# bristol_longshot_development.net
KiCad netlist of a schematic drawn in EAGLE
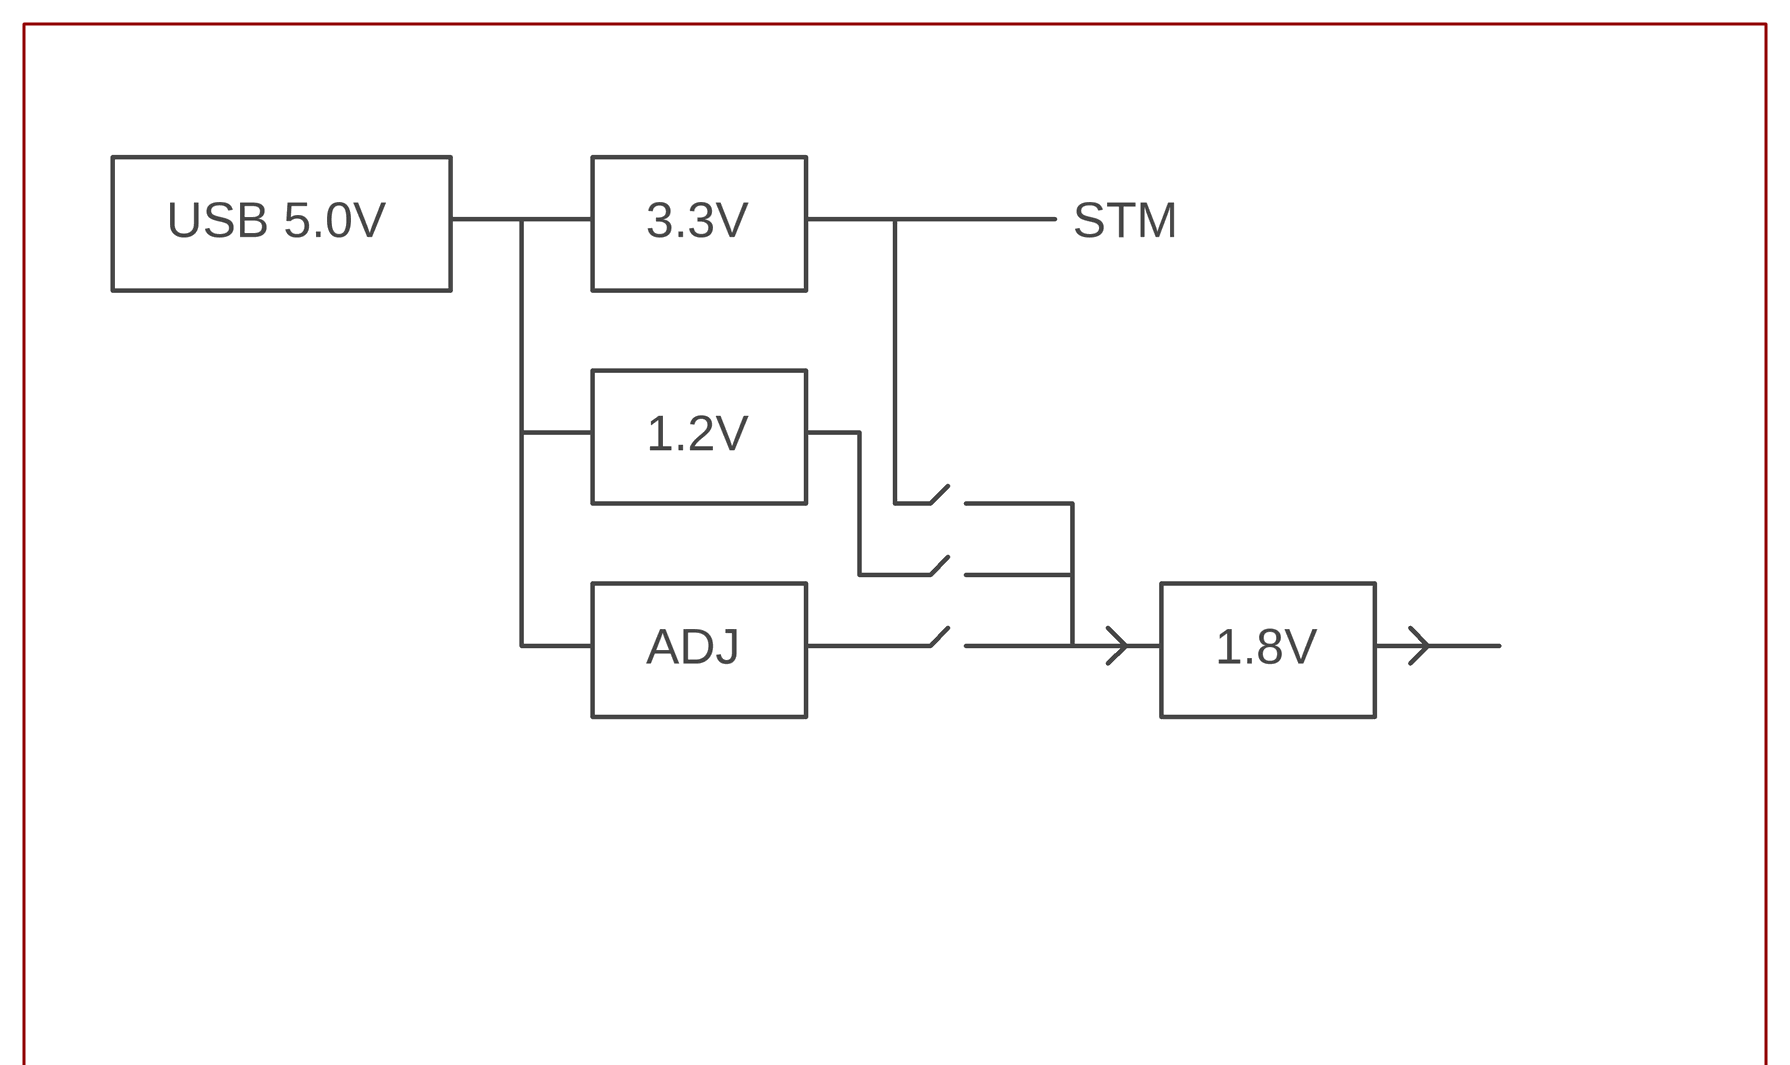
[diagram p0: schematic, sheet 1, part 1 of 3]
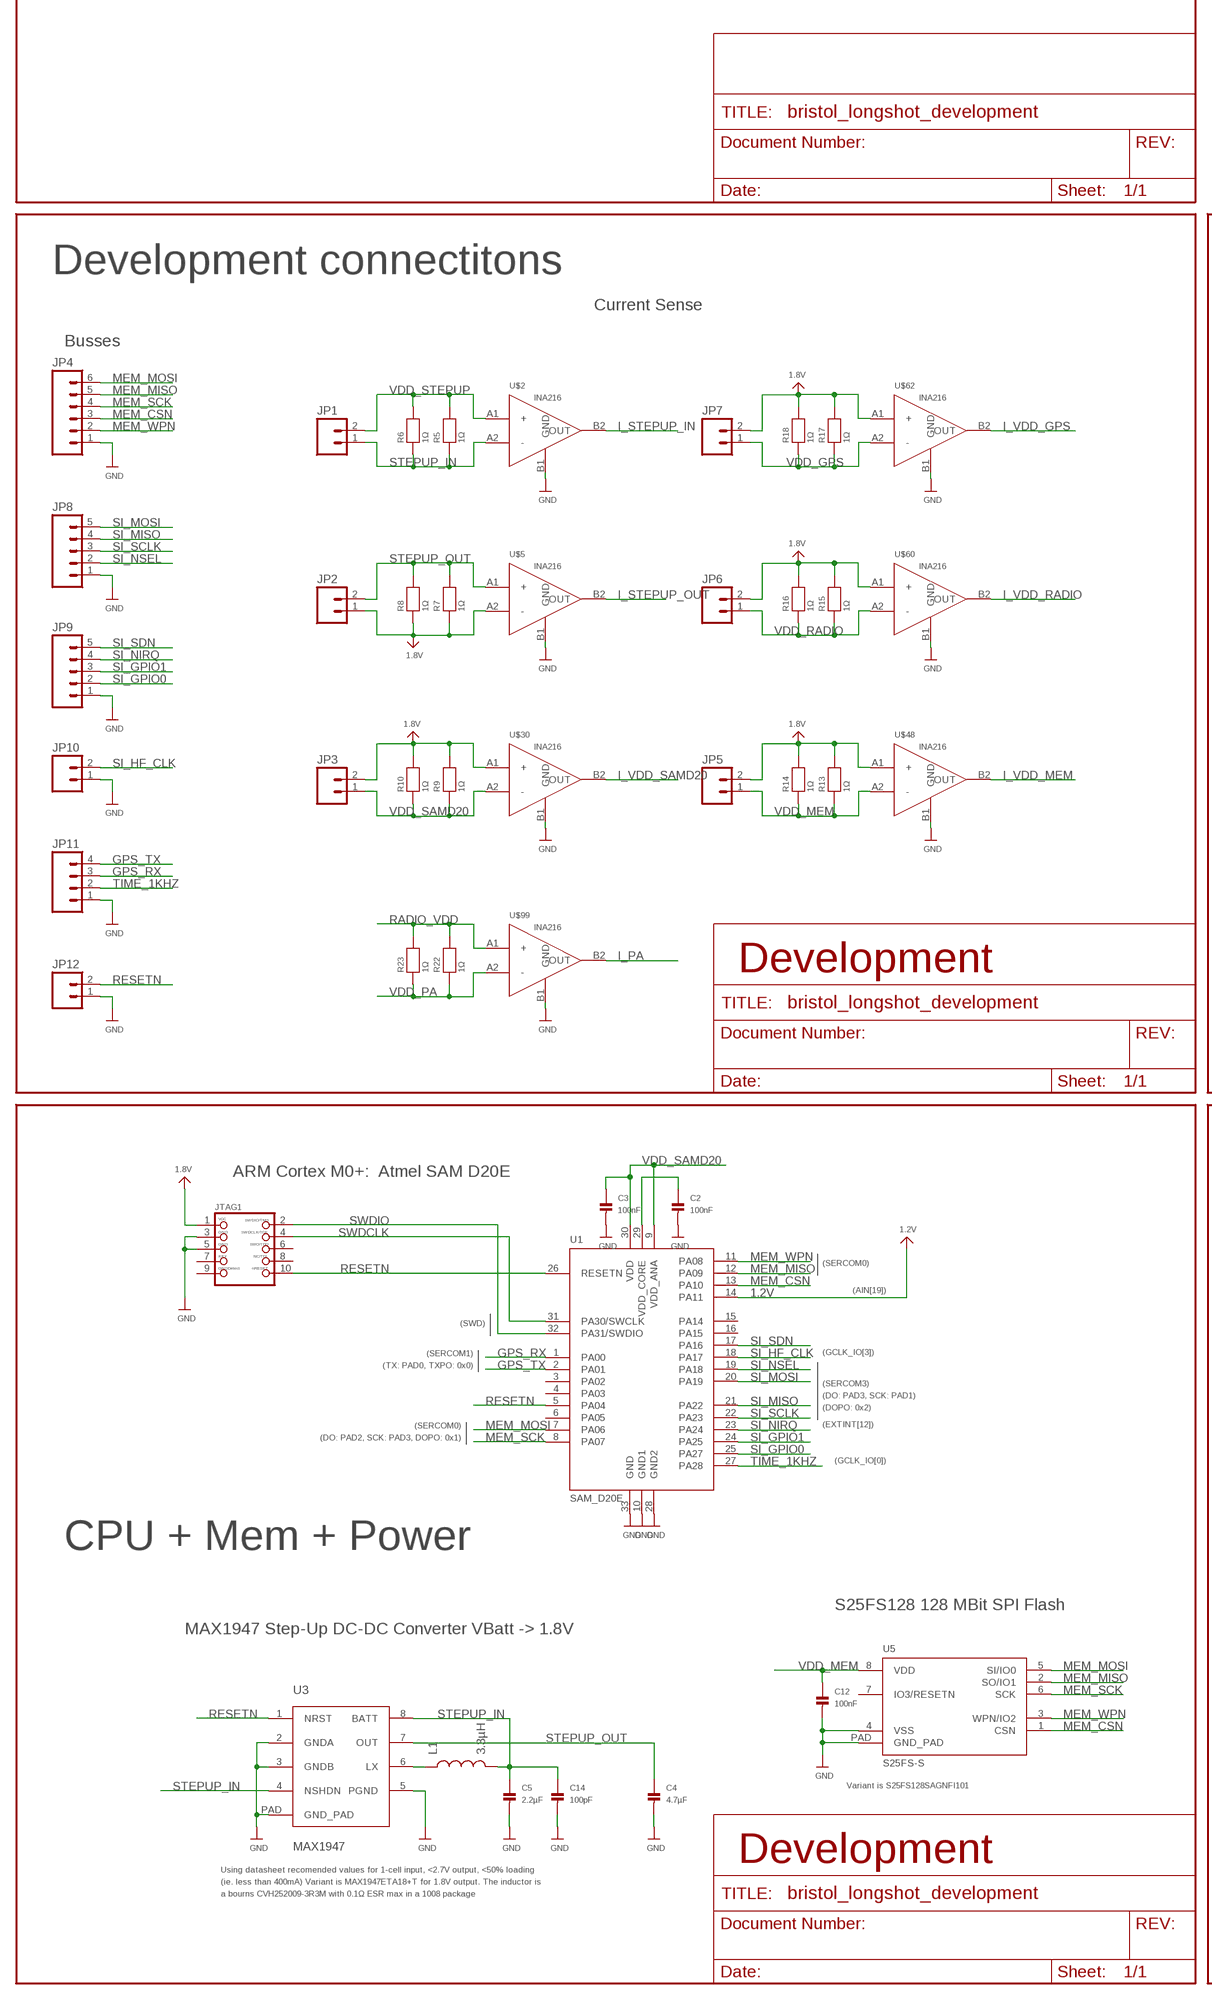
[diagram p1: schematic, sheet 1, part 2 of 3]
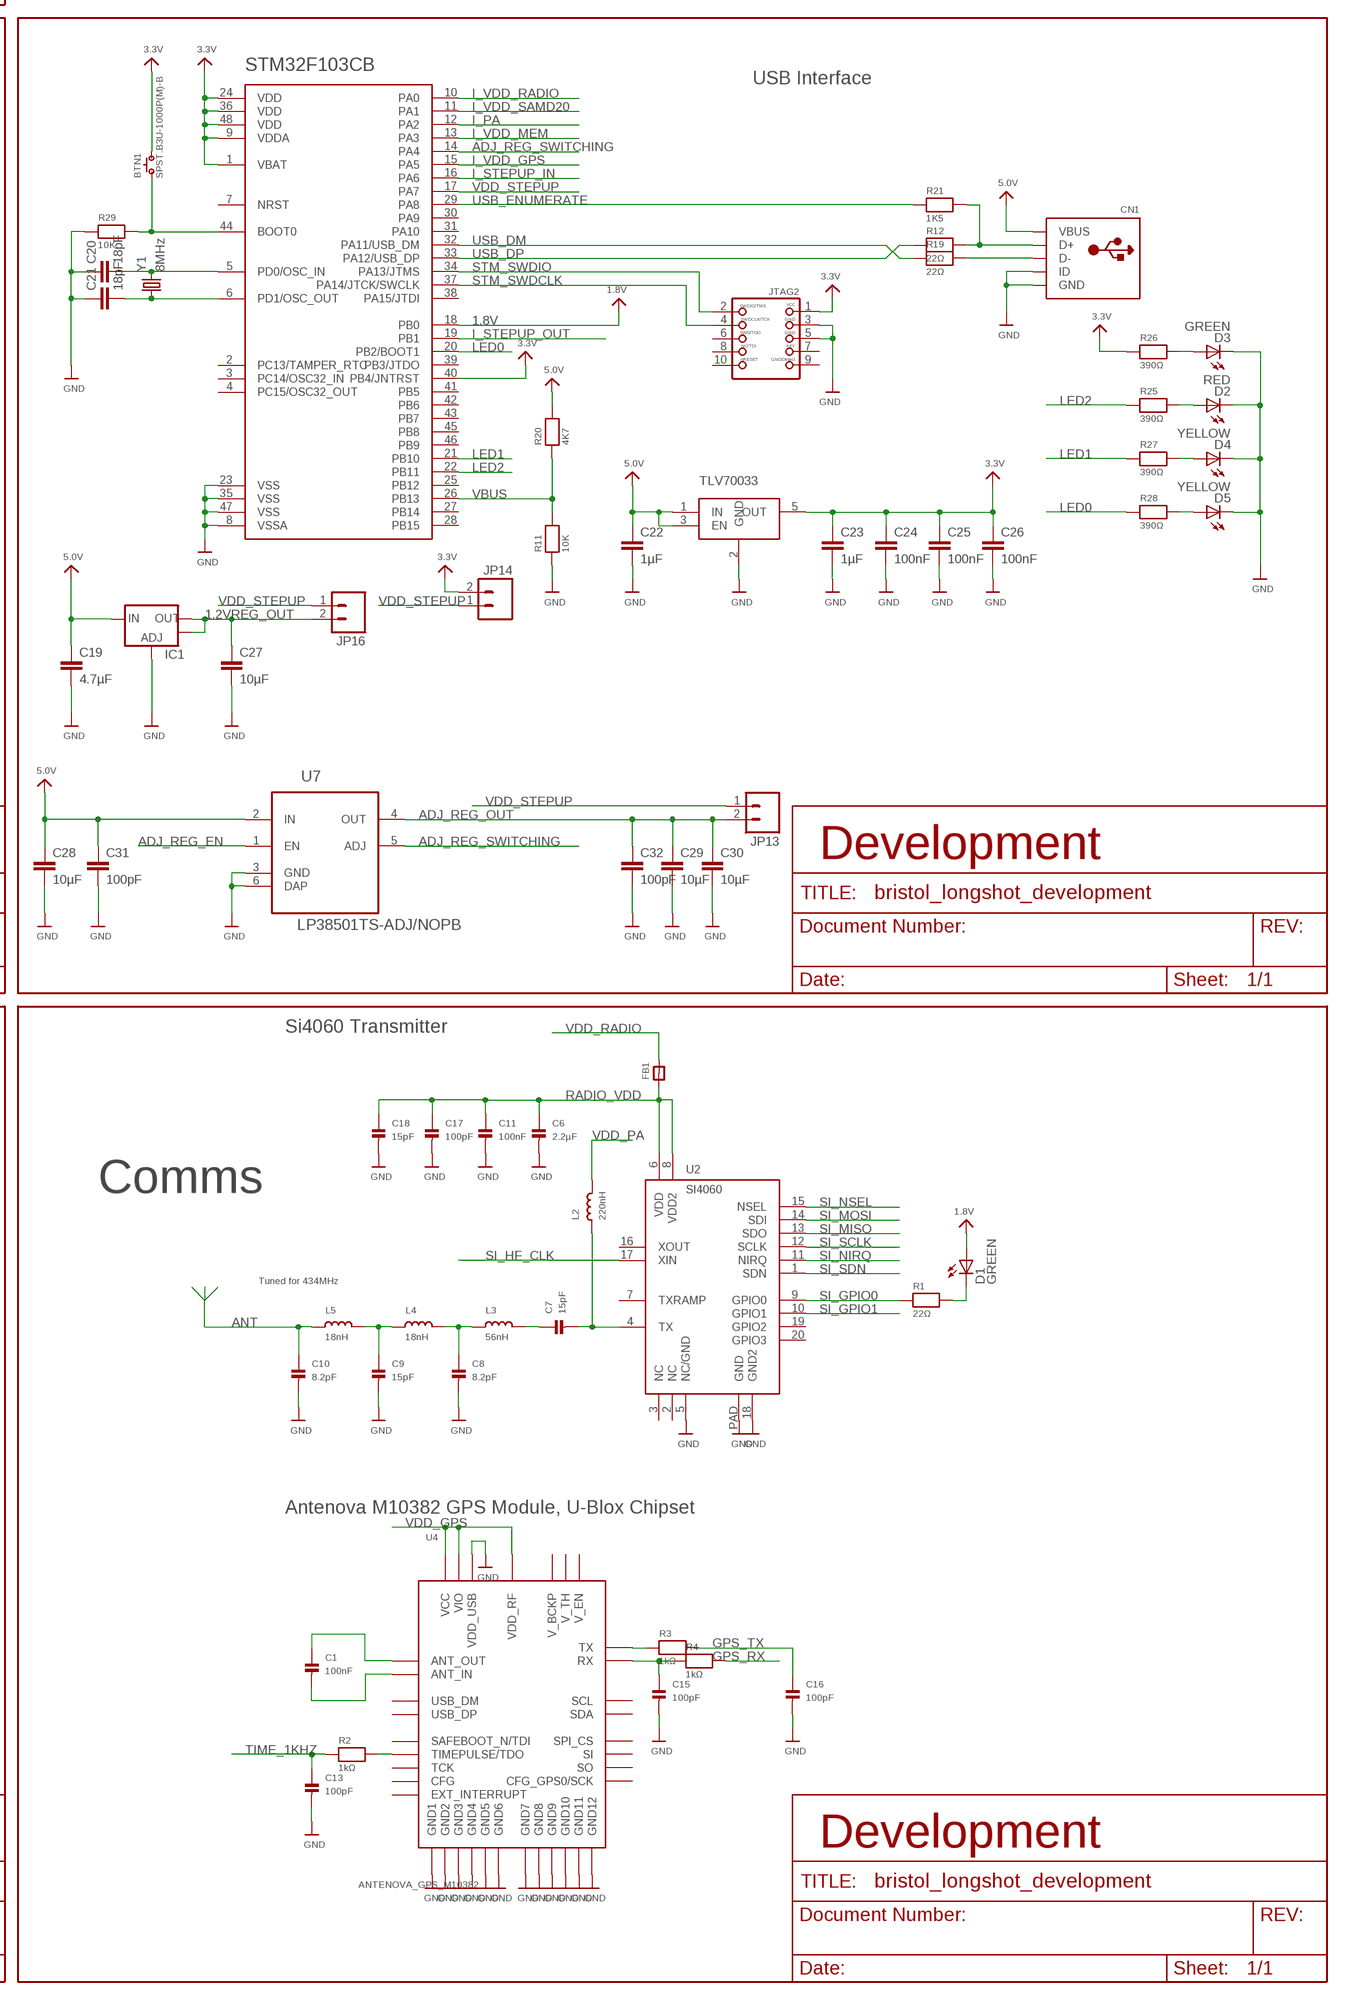
[diagram p2: schematic, sheet 1, part 3 of 3]

(export (version "E")
  (design (tool "Eeschema 10.0.6"))
  (components
    (comp (ref "BTN1")
      (value "SPST.B3U-1000P(M)-B")
      (footprint "eagle-import:B3U-1000P(M)-B")
      (libsource (lib "eagle-import") (part "SPST.B3U-1000P(M)-B"))
    )
    (comp (ref "C1")
      (value "100nF")
      (footprint "eagle-import:_0402")
      (libsource (lib "eagle-import") (part "CAP_CERAMIC_0402"))
    )
    (comp (ref "C2")
      (value "100nF")
      (footprint "eagle-import:_0402")
      (libsource (lib "eagle-import") (part "CAP_CERAMIC_0402"))
    )
    (comp (ref "C3")
      (value "100nF")
      (footprint "eagle-import:_0402")
      (libsource (lib "eagle-import") (part "CAP_CERAMIC_0402"))
    )
    (comp (ref "C4")
      (value "4.7µF")
      (footprint "eagle-import:_0402")
      (libsource (lib "eagle-import") (part "CAP_CERAMIC_0402"))
    )
    (comp (ref "C5")
      (value "2.2µF")
      (footprint "eagle-import:_0402")
      (libsource (lib "eagle-import") (part "CAP_CERAMIC_0402"))
    )
    (comp (ref "C6")
      (value "2.2µF")
      (footprint "eagle-import:_0402")
      (libsource (lib "eagle-import") (part "CAP_CERAMIC_0402"))
    )
    (comp (ref "C7")
      (value "15pF")
      (footprint "eagle-import:_0402")
      (libsource (lib "eagle-import") (part "CAP_CERAMIC_0402"))
    )
    (comp (ref "C8")
      (value "8.2pF")
      (footprint "eagle-import:_0402")
      (libsource (lib "eagle-import") (part "CAP_CERAMIC_0402"))
    )
    (comp (ref "C9")
      (value "15pF")
      (footprint "eagle-import:_0402")
      (libsource (lib "eagle-import") (part "CAP_CERAMIC_0402"))
    )
    (comp (ref "C10")
      (value "8.2pF")
      (footprint "eagle-import:_0402")
      (libsource (lib "eagle-import") (part "CAP_CERAMIC_0402"))
    )
    (comp (ref "C11")
      (value "100nF")
      (footprint "eagle-import:_0402")
      (libsource (lib "eagle-import") (part "CAP_CERAMIC_0402"))
    )
    (comp (ref "C12")
      (value "100nF")
      (footprint "eagle-import:_0402")
      (libsource (lib "eagle-import") (part "CAP_CERAMIC_0402"))
    )
    (comp (ref "C13")
      (value "100pF")
      (footprint "eagle-import:_0402")
      (libsource (lib "eagle-import") (part "CAP_CERAMIC_0402"))
    )
    (comp (ref "C14")
      (value "100pF")
      (footprint "eagle-import:_0402")
      (libsource (lib "eagle-import") (part "CAP_CERAMIC_0402"))
    )
    (comp (ref "C15")
      (value "100pF")
      (footprint "eagle-import:_0402")
      (libsource (lib "eagle-import") (part "CAP_CERAMIC_0402"))
    )
    (comp (ref "C16")
      (value "100pF")
      (footprint "eagle-import:_0402")
      (libsource (lib "eagle-import") (part "CAP_CERAMIC_0402"))
    )
    (comp (ref "C17")
      (value "100pF")
      (footprint "eagle-import:_0402")
      (libsource (lib "eagle-import") (part "CAP_CERAMIC_0402"))
    )
    (comp (ref "C18")
      (value "15pF")
      (footprint "eagle-import:_0402")
      (libsource (lib "eagle-import") (part "CAP_CERAMIC_0402"))
    )
    (comp (ref "C19")
      (value "4.7µF")
      (footprint "eagle-import:C0603K")
      (libsource (lib "eagle-import") (part "C-EUC0603K"))
    )
    (comp (ref "C20")
      (value "18pF")
      (footprint "eagle-import:C0603K")
      (libsource (lib "eagle-import") (part "C-EUC0603K"))
    )
    (comp (ref "C21")
      (value "18pF")
      (footprint "eagle-import:C0603K")
      (libsource (lib "eagle-import") (part "C-EUC0603K"))
    )
    (comp (ref "C22")
      (value "1µF")
      (footprint "eagle-import:C0603K")
      (libsource (lib "eagle-import") (part "C-EUC0603K"))
    )
    (comp (ref "C23")
      (value "1µF")
      (footprint "eagle-import:C0603K")
      (libsource (lib "eagle-import") (part "C-EUC0603K"))
    )
    (comp (ref "C24")
      (value "100nF")
      (footprint "eagle-import:C0603K")
      (libsource (lib "eagle-import") (part "C-EUC0603K"))
    )
    (comp (ref "C25")
      (value "100nF")
      (footprint "eagle-import:C0603K")
      (libsource (lib "eagle-import") (part "C-EUC0603K"))
    )
    (comp (ref "C26")
      (value "100nF")
      (footprint "eagle-import:C0603K")
      (libsource (lib "eagle-import") (part "C-EUC0603K"))
    )
    (comp (ref "C27")
      (value "10µF")
      (footprint "eagle-import:C0603K")
      (libsource (lib "eagle-import") (part "C-EUC0603K"))
    )
    (comp (ref "C28")
      (value "10µF")
      (footprint "eagle-import:C0603K")
      (libsource (lib "eagle-import") (part "C-EUC0603K"))
    )
    (comp (ref "C29")
      (value "10µF")
      (footprint "eagle-import:C0603K")
      (libsource (lib "eagle-import") (part "C-EUC0603K"))
    )
    (comp (ref "C30")
      (value "10µF")
      (footprint "eagle-import:C0603K")
      (libsource (lib "eagle-import") (part "C-EUC0603K"))
    )
    (comp (ref "C31")
      (value "100pF")
      (footprint "eagle-import:C0603K")
      (libsource (lib "eagle-import") (part "C-EUC0603K"))
    )
    (comp (ref "C32")
      (value "100pF")
      (footprint "eagle-import:C0603K")
      (libsource (lib "eagle-import") (part "C-EUC0603K"))
    )
    (comp (ref "CN1")
      (value "USBMINIB")
      (footprint "eagle-import:USB-MINIB")
      (libsource (lib "eagle-import") (part "USBMINIB"))
    )
    (comp (ref "D1")
      (value "GREEN")
      (footprint "eagle-import:CHIPLED_0603")
      (libsource (lib "eagle-import") (part "LEDCHIPLED_0603"))
    )
    (comp (ref "D2")
      (value "RED")
      (footprint "eagle-import:CHIPLED_0603")
      (libsource (lib "eagle-import") (part "LEDCHIPLED_0603"))
    )
    (comp (ref "D3")
      (value "GREEN")
      (footprint "eagle-import:CHIPLED_0603")
      (libsource (lib "eagle-import") (part "LEDCHIPLED_0603"))
    )
    (comp (ref "D4")
      (value "YELLOW")
      (footprint "eagle-import:CHIPLED_0603")
      (libsource (lib "eagle-import") (part "LEDCHIPLED_0603"))
    )
    (comp (ref "D5")
      (value "YELLOW")
      (footprint "eagle-import:CHIPLED_0603")
      (libsource (lib "eagle-import") (part "LEDCHIPLED_0603"))
    )
    (comp (ref "FB1")
      (value "FERRITE_0402")
      (footprint "eagle-import:_0402")
      (libsource (lib "eagle-import") (part "FERRITE_0402"))
    )
    (comp (ref "IC1")
      (value "V_REG_LM1117SOT223")
      (footprint "eagle-import:SOT223")
      (libsource (lib "eagle-import") (part "V_REG_LM1117SOT223"))
    )
    (comp (ref "IC3")
      (value "TLV70033DCK")
      (footprint "eagle-import:SC70-5L")
      (libsource (lib "eagle-import") (part "TLV700DCK"))
    )
    (comp (ref "JP1")
      (value "M02LOCK")
      (footprint "eagle-import:1X02_LOCK")
      (libsource (lib "eagle-import") (part "M02LOCK"))
    )
    (comp (ref "JP2")
      (value "M02LOCK")
      (footprint "eagle-import:1X02_LOCK")
      (libsource (lib "eagle-import") (part "M02LOCK"))
    )
    (comp (ref "JP3")
      (value "M02LOCK")
      (footprint "eagle-import:1X02_LOCK")
      (libsource (lib "eagle-import") (part "M02LOCK"))
    )
    (comp (ref "JP4")
      (value "M06LOCK")
      (footprint "eagle-import:1X06_LOCK")
      (libsource (lib "eagle-import") (part "M06LOCK"))
    )
    (comp (ref "JP5")
      (value "M02LOCK")
      (footprint "eagle-import:1X02_LOCK")
      (libsource (lib "eagle-import") (part "M02LOCK"))
    )
    (comp (ref "JP6")
      (value "M02LOCK")
      (footprint "eagle-import:1X02_LOCK")
      (libsource (lib "eagle-import") (part "M02LOCK"))
    )
    (comp (ref "JP7")
      (value "M02LOCK")
      (footprint "eagle-import:1X02_LOCK")
      (libsource (lib "eagle-import") (part "M02LOCK"))
    )
    (comp (ref "JP8")
      (value "M05LOCK")
      (footprint "eagle-import:1X05_LOCK")
      (libsource (lib "eagle-import") (part "M05LOCK"))
    )
    (comp (ref "JP9")
      (value "M05LOCK")
      (footprint "eagle-import:1X05_LOCK")
      (libsource (lib "eagle-import") (part "M05LOCK"))
    )
    (comp (ref "JP10")
      (value "M02LOCK")
      (footprint "eagle-import:1X02_LOCK")
      (libsource (lib "eagle-import") (part "M02LOCK"))
    )
    (comp (ref "JP11")
      (value "M04LOCK")
      (footprint "eagle-import:1X04_LOCK")
      (libsource (lib "eagle-import") (part "M04LOCK"))
    )
    (comp (ref "JP12")
      (value "M02LOCK")
      (footprint "eagle-import:1X02_LOCK")
      (libsource (lib "eagle-import") (part "M02LOCK"))
    )
    (comp (ref "JP13")
      (value "M02LOCK")
      (footprint "eagle-import:1X02_LOCK")
      (libsource (lib "eagle-import") (part "M02LOCK"))
    )
    (comp (ref "JP14")
      (value "M02LOCK")
      (footprint "eagle-import:1X02_LOCK")
      (libsource (lib "eagle-import") (part "M02LOCK"))
    )
    (comp (ref "JP16")
      (value "M02LOCK")
      (footprint "eagle-import:1X02_LOCK")
      (libsource (lib "eagle-import") (part "M02LOCK"))
    )
    (comp (ref "JTAG1")
      (value "JTAG-CORTEXM3SMT")
      (footprint "eagle-import:2X05_1.27MM_SMT")
      (libsource (lib "eagle-import") (part "JTAG-CORTEXM3SMT"))
    )
    (comp (ref "JTAG2")
      (value "JTAG-CORTEXM3SMT")
      (footprint "eagle-import:2X05_1.27MM_SMT")
      (libsource (lib "eagle-import") (part "JTAG-CORTEXM3SMT"))
    )
    (comp (ref "L1")
      (value "3.3µH")
      (footprint "eagle-import:1007")
      (libsource (lib "eagle-import") (part "INDUCTOR1007"))
    )
    (comp (ref "L2")
      (value "220nH")
      (footprint "eagle-import:_0402")
      (libsource (lib "eagle-import") (part "INDUCTOR_0402"))
    )
    (comp (ref "L3")
      (value "56nH")
      (footprint "eagle-import:_0402")
      (libsource (lib "eagle-import") (part "INDUCTOR_0402"))
    )
    (comp (ref "L4")
      (value "18nH")
      (footprint "eagle-import:_0402")
      (libsource (lib "eagle-import") (part "INDUCTOR_0402"))
    )
    (comp (ref "L5")
      (value "18nH")
      (footprint "eagle-import:_0402")
      (libsource (lib "eagle-import") (part "INDUCTOR_0402"))
    )
    (comp (ref "R1")
      (value "22Ω")
      (footprint "eagle-import:_0402")
      (libsource (lib "eagle-import") (part "RESISTOR_0402"))
    )
    (comp (ref "R2")
      (value "1kΩ")
      (footprint "eagle-import:_0402")
      (libsource (lib "eagle-import") (part "RESISTOR_0402"))
    )
    (comp (ref "R3")
      (value "1kΩ")
      (footprint "eagle-import:_0402")
      (libsource (lib "eagle-import") (part "RESISTOR_0402"))
    )
    (comp (ref "R4")
      (value "1kΩ")
      (footprint "eagle-import:_0402")
      (libsource (lib "eagle-import") (part "RESISTOR_0402"))
    )
    (comp (ref "R5")
      (value "1Ω")
      (footprint "eagle-import:_0402")
      (libsource (lib "eagle-import") (part "RESISTOR_0402"))
    )
    (comp (ref "R6")
      (value "1Ω")
      (footprint "eagle-import:_0402")
      (libsource (lib "eagle-import") (part "RESISTOR_0402"))
    )
    (comp (ref "R7")
      (value "1Ω")
      (footprint "eagle-import:_0402")
      (libsource (lib "eagle-import") (part "RESISTOR_0402"))
    )
    (comp (ref "R8")
      (value "1Ω")
      (footprint "eagle-import:_0402")
      (libsource (lib "eagle-import") (part "RESISTOR_0402"))
    )
    (comp (ref "R9")
      (value "1Ω")
      (footprint "eagle-import:_0402")
      (libsource (lib "eagle-import") (part "RESISTOR_0402"))
    )
    (comp (ref "R10")
      (value "1Ω")
      (footprint "eagle-import:_0402")
      (libsource (lib "eagle-import") (part "RESISTOR_0402"))
    )
    (comp (ref "R11")
      (value "10K")
      (footprint "eagle-import:0603-MINI")
      (libsource (lib "eagle-import") (part "RESISTOR0603MINI"))
    )
    (comp (ref "R12")
      (value "22Ω")
      (footprint "eagle-import:0603-MINI")
      (libsource (lib "eagle-import") (part "RESISTOR0603MINI"))
    )
    (comp (ref "R13")
      (value "1Ω")
      (footprint "eagle-import:_0402")
      (libsource (lib "eagle-import") (part "RESISTOR_0402"))
    )
    (comp (ref "R14")
      (value "1Ω")
      (footprint "eagle-import:_0402")
      (libsource (lib "eagle-import") (part "RESISTOR_0402"))
    )
    (comp (ref "R15")
      (value "1Ω")
      (footprint "eagle-import:_0402")
      (libsource (lib "eagle-import") (part "RESISTOR_0402"))
    )
    (comp (ref "R16")
      (value "1Ω")
      (footprint "eagle-import:_0402")
      (libsource (lib "eagle-import") (part "RESISTOR_0402"))
    )
    (comp (ref "R17")
      (value "1Ω")
      (footprint "eagle-import:_0402")
      (libsource (lib "eagle-import") (part "RESISTOR_0402"))
    )
    (comp (ref "R18")
      (value "1Ω")
      (footprint "eagle-import:_0402")
      (libsource (lib "eagle-import") (part "RESISTOR_0402"))
    )
    (comp (ref "R19")
      (value "22Ω")
      (footprint "eagle-import:0603-MINI")
      (libsource (lib "eagle-import") (part "RESISTOR0603MINI"))
    )
    (comp (ref "R20")
      (value "4K7")
      (footprint "eagle-import:0603-MINI")
      (libsource (lib "eagle-import") (part "RESISTOR0603MINI"))
    )
    (comp (ref "R21")
      (value "1K5")
      (footprint "eagle-import:0603-MINI")
      (libsource (lib "eagle-import") (part "RESISTOR0603MINI"))
    )
    (comp (ref "R22")
      (value "1Ω")
      (footprint "eagle-import:_0402")
      (libsource (lib "eagle-import") (part "RESISTOR_0402"))
    )
    (comp (ref "R23")
      (value "1Ω")
      (footprint "eagle-import:_0402")
      (libsource (lib "eagle-import") (part "RESISTOR_0402"))
    )
    (comp (ref "R25")
      (value "390Ω")
      (footprint "eagle-import:0603-MINI")
      (libsource (lib "eagle-import") (part "RESISTOR0603MINI"))
    )
    (comp (ref "R26")
      (value "390Ω")
      (footprint "eagle-import:0603-MINI")
      (libsource (lib "eagle-import") (part "RESISTOR0603MINI"))
    )
    (comp (ref "R27")
      (value "390Ω")
      (footprint "eagle-import:0603-MINI")
      (libsource (lib "eagle-import") (part "RESISTOR0603MINI"))
    )
    (comp (ref "R28")
      (value "390Ω")
      (footprint "eagle-import:0603-MINI")
      (libsource (lib "eagle-import") (part "RESISTOR0603MINI"))
    )
    (comp (ref "R29")
      (value "10K")
      (footprint "eagle-import:0603-MINI")
      (libsource (lib "eagle-import") (part "RESISTOR0603MINI"))
    )
    (comp (ref "U$2")
      (value "INA216")
      (footprint "eagle-import:WCSP-4")
      (libsource (lib "eagle-import") (part "INA216"))
    )
    (comp (ref "U$5")
      (value "INA216")
      (footprint "eagle-import:WCSP-4")
      (libsource (lib "eagle-import") (part "INA216"))
    )
    (comp (ref "U$30")
      (value "INA216")
      (footprint "eagle-import:WCSP-4")
      (libsource (lib "eagle-import") (part "INA216"))
    )
    (comp (ref "U$48")
      (value "INA216")
      (footprint "eagle-import:WCSP-4")
      (libsource (lib "eagle-import") (part "INA216"))
    )
    (comp (ref "U$60")
      (value "INA216")
      (footprint "eagle-import:WCSP-4")
      (libsource (lib "eagle-import") (part "INA216"))
    )
    (comp (ref "U$62")
      (value "INA216")
      (footprint "eagle-import:WCSP-4")
      (libsource (lib "eagle-import") (part "INA216"))
    )
    (comp (ref "U$99")
      (value "INA216")
      (footprint "eagle-import:WCSP-4")
      (libsource (lib "eagle-import") (part "INA216"))
    )
    (comp (ref "U1")
      (value "SAM_D20E")
      (footprint "eagle-import:QFN32_5MM")
      (libsource (lib "eagle-import") (part "SAM_D20E"))
    )
    (comp (ref "U2")
      (value "SI4060")
      (footprint "eagle-import:QFN20")
      (libsource (lib "eagle-import") (part "SI4060"))
    )
    (comp (ref "U3")
      (value "MAX1947")
      (footprint "eagle-import:TDFN8")
      (libsource (lib "eagle-import") (part "MAX1947"))
    )
    (comp (ref "U4")
      (value "ANTENOVA_GPS_M10382")
      (footprint "eagle-import:ANTENOVA_GPS_M10382")
      (libsource (lib "eagle-import") (part "ANTENOVA_GPS_M10382"))
    )
    (comp (ref "U5")
      (value "S25FS-S")
      (footprint "eagle-import:WSON8")
      (libsource (lib "eagle-import") (part "S25FS-S"))
    )
    (comp (ref "U6")
      (value "STM32F_48PIN")
      (footprint "eagle-import:TQFP48")
      (libsource (lib "eagle-import") (part "STM32F_48PIN"))
    )
    (comp (ref "U7")
      (value "LP38501TS-ADJ/NOPB")
      (footprint "eagle-import:TO170P1435X457-6N")
      (libsource (lib "eagle-import") (part "LP38501TS-ADJ/NOPB"))
    )
    (comp (ref "Y1")
      (value "8MHz")
      (footprint "eagle-import:CRYSTAL-SMD-5X3")
      (libsource (lib "eagle-import") (part "CRYSTAL5X3"))
    )
  )
  (nets
    (net (code "1") (name "/1.2VREG_OUT") (class "Default")
      (node (ref "C27") (pin "1") (pinfunction "1_1") (pintype "passive"))
      (node (ref "IC1") (pin "2") (pinfunction "OUT_2") (pintype "output"))
      (node (ref "IC1") (pin "4") (pinfunction "OUT_4") (pintype "output"))
      (node (ref "JP16") (pin "2") (pinfunction "2_2") (pintype "passive"))
    )
    (net (code "2") (name "/ADJ_REG_EN") (class "Default")
      (node (ref "U7") (pin "1") (pinfunction "EN_1") (pintype "input"))
    )
    (net (code "3") (name "/ADJ_REG_OUT") (class "Default")
      (node (ref "C29") (pin "1") (pinfunction "1_1") (pintype "passive"))
      (node (ref "C30") (pin "1") (pinfunction "1_1") (pintype "passive"))
      (node (ref "C32") (pin "1") (pinfunction "1_1") (pintype "passive"))
      (node (ref "JP13") (pin "2") (pinfunction "2_2") (pintype "passive"))
      (node (ref "U7") (pin "4") (pinfunction "OUT_4") (pintype "output"))
    )
    (net (code "4") (name "/ADJ_REG_SWITCHING") (class "Default")
      (node (ref "U6") (pin "14") (pinfunction "PA4_14") (pintype "bidirectional"))
      (node (ref "U7") (pin "5") (pinfunction "ADJ_5") (pintype "input"))
    )
    (net (code "5") (name "/ANT") (class "Default")
      (node (ref "C10") (pin "1") (pinfunction "P$1_1") (pintype "passive"))
      (node (ref "L5") (pin "1") (pinfunction "1_1") (pintype "passive"))
    )
    (net (code "6") (name "/GPS_RX") (class "Default")
      (node (ref "JP11") (pin "3") (pinfunction "3_3") (pintype "passive"))
      (node (ref "R4") (pin "2") (pinfunction "2_2") (pintype "passive"))
      (node (ref "U1") (pin "1") (pinfunction "PA00_1") (pintype "bidirectional"))
    )
    (net (code "7") (name "/GPS_TX") (class "Default")
      (node (ref "C16") (pin "1") (pinfunction "P$1_1") (pintype "passive"))
      (node (ref "JP11") (pin "4") (pinfunction "4_4") (pintype "passive"))
      (node (ref "R3") (pin "2") (pinfunction "2_2") (pintype "passive"))
      (node (ref "U1") (pin "2") (pinfunction "PA01_2") (pintype "bidirectional"))
    )
    (net (code "8") (name "/I_PA") (class "Default")
      (node (ref "U$99") (pin "B2") (pinfunction "OUT_B2") (pintype "bidirectional"))
      (node (ref "U6") (pin "12") (pinfunction "PA2_12") (pintype "bidirectional"))
    )
    (net (code "9") (name "/I_STEPUP_IN") (class "Default")
      (node (ref "U$2") (pin "B2") (pinfunction "OUT_B2") (pintype "bidirectional"))
      (node (ref "U6") (pin "16") (pinfunction "PA6_16") (pintype "bidirectional"))
    )
    (net (code "10") (name "/I_STEPUP_OUT") (class "Default")
      (node (ref "U$5") (pin "B2") (pinfunction "OUT_B2") (pintype "bidirectional"))
      (node (ref "U6") (pin "19") (pinfunction "PB1_19") (pintype "bidirectional"))
    )
    (net (code "11") (name "/I_VDD_GPS") (class "Default")
      (node (ref "U$62") (pin "B2") (pinfunction "OUT_B2") (pintype "bidirectional"))
      (node (ref "U6") (pin "15") (pinfunction "PA5_15") (pintype "bidirectional"))
    )
    (net (code "12") (name "/I_VDD_MEM") (class "Default")
      (node (ref "U$48") (pin "B2") (pinfunction "OUT_B2") (pintype "bidirectional"))
      (node (ref "U6") (pin "13") (pinfunction "PA3_13") (pintype "bidirectional"))
    )
    (net (code "13") (name "/I_VDD_RADIO") (class "Default")
      (node (ref "U$60") (pin "B2") (pinfunction "OUT_B2") (pintype "bidirectional"))
      (node (ref "U6") (pin "10") (pinfunction "PA0_10") (pintype "bidirectional"))
    )
    (net (code "14") (name "/I_VDD_SAMD20") (class "Default")
      (node (ref "U$30") (pin "B2") (pinfunction "OUT_B2") (pintype "bidirectional"))
      (node (ref "U6") (pin "11") (pinfunction "PA1_11") (pintype "bidirectional"))
    )
    (net (code "15") (name "/LED0") (class "Default")
      (node (ref "R28") (pin "1") (pinfunction "1_1") (pintype "passive"))
      (node (ref "U6") (pin "20") (pinfunction "PB2/BOOT1_20") (pintype "bidirectional"))
    )
    (net (code "16") (name "/LED1") (class "Default")
      (node (ref "R27") (pin "1") (pinfunction "1_1") (pintype "passive"))
      (node (ref "U6") (pin "21") (pinfunction "PB10_21") (pintype "bidirectional"))
    )
    (net (code "17") (name "/LED2") (class "Default")
      (node (ref "R25") (pin "1") (pinfunction "1_1") (pintype "passive"))
      (node (ref "U6") (pin "22") (pinfunction "PB11_22") (pintype "bidirectional"))
    )
    (net (code "18") (name "/MEM_CSN") (class "Default")
      (node (ref "JP4") (pin "3") (pinfunction "3_3") (pintype "passive"))
      (node (ref "U1") (pin "13") (pinfunction "PA10_13") (pintype "bidirectional"))
      (node (ref "U5") (pin "1") (pinfunction "CSN_1") (pintype "input"))
    )
    (net (code "19") (name "/MEM_MISO") (class "Default")
      (node (ref "JP4") (pin "5") (pinfunction "5_5") (pintype "passive"))
      (node (ref "U1") (pin "12") (pinfunction "PA09_12") (pintype "bidirectional"))
      (node (ref "U5") (pin "2") (pinfunction "SO/IO1_2") (pintype "output"))
    )
    (net (code "20") (name "/MEM_MOSI") (class "Default")
      (node (ref "JP4") (pin "6") (pinfunction "6_6") (pintype "passive"))
      (node (ref "U1") (pin "7") (pinfunction "PA06_7") (pintype "bidirectional"))
      (node (ref "U5") (pin "5") (pinfunction "SI/IO0_5") (pintype "bidirectional"))
    )
    (net (code "21") (name "/MEM_SCK") (class "Default")
      (node (ref "JP4") (pin "4") (pinfunction "4_4") (pintype "passive"))
      (node (ref "U1") (pin "8") (pinfunction "PA07_8") (pintype "bidirectional"))
      (node (ref "U5") (pin "6") (pinfunction "SCK_6") (pintype "input"))
    )
    (net (code "22") (name "/MEM_WPN") (class "Default")
      (node (ref "JP4") (pin "2") (pinfunction "2_2") (pintype "passive"))
      (node (ref "U1") (pin "11") (pinfunction "PA08_11") (pintype "bidirectional"))
      (node (ref "U5") (pin "3") (pinfunction "WPN/IO2_3") (pintype "output"))
    )
    (net (code "23") (name "/RADIO_VDD") (class "Default")
      (node (ref "C11") (pin "1") (pinfunction "P$1_1") (pintype "passive"))
      (node (ref "C17") (pin "1") (pinfunction "P$1_1") (pintype "passive"))
      (node (ref "C18") (pin "1") (pinfunction "P$1_1") (pintype "passive"))
      (node (ref "C6") (pin "1") (pinfunction "P$1_1") (pintype "passive"))
      (node (ref "FB1") (pin "1") (pinfunction "P$1_1") (pintype "passive"))
      (node (ref "R22") (pin "2") (pinfunction "2_2") (pintype "passive"))
      (node (ref "R23") (pin "2") (pinfunction "2_2") (pintype "passive"))
      (node (ref "U$99") (pin "A1") (pinfunction "+_A1") (pintype "bidirectional"))
      (node (ref "U2") (pin "6") (pinfunction "VDD_6") (pintype "power_in"))
      (node (ref "U2") (pin "8") (pinfunction "VDD2_8") (pintype "power_in"))
    )
    (net (code "24") (name "/RESETN") (class "Default")
      (node (ref "JP12") (pin "2") (pinfunction "2_2") (pintype "passive"))
      (node (ref "JTAG1") (pin "10") (pinfunction "10_10") (pintype "passive"))
      (node (ref "U1") (pin "26") (pinfunction "RESETN_26") (pintype "input"))
      (node (ref "U1") (pin "5") (pinfunction "PA04_5") (pintype "bidirectional"))
      (node (ref "U3") (pin "1") (pinfunction "NRST_1") (pintype "bidirectional"))
    )
    (net (code "25") (name "/SI_GPIO0") (class "Default")
      (node (ref "JP9") (pin "2") (pinfunction "2_2") (pintype "passive"))
      (node (ref "R1") (pin "1") (pinfunction "1_1") (pintype "passive"))
      (node (ref "U1") (pin "25") (pinfunction "PA27_25") (pintype "bidirectional"))
      (node (ref "U2") (pin "9") (pinfunction "GPIO0_9") (pintype "bidirectional"))
    )
    (net (code "26") (name "/SI_GPIO1") (class "Default")
      (node (ref "JP9") (pin "3") (pinfunction "3_3") (pintype "passive"))
      (node (ref "U1") (pin "24") (pinfunction "PA25_24") (pintype "bidirectional"))
      (node (ref "U2") (pin "10") (pinfunction "GPIO1_10") (pintype "bidirectional"))
    )
    (net (code "27") (name "/SI_HF_CLK") (class "Default")
      (node (ref "JP10") (pin "2") (pinfunction "2_2") (pintype "passive"))
      (node (ref "U1") (pin "18") (pinfunction "PA17_18") (pintype "bidirectional"))
      (node (ref "U2") (pin "17") (pinfunction "XIN_17") (pintype "input"))
    )
    (net (code "28") (name "/SI_MISO") (class "Default")
      (node (ref "JP8") (pin "4") (pinfunction "4_4") (pintype "passive"))
      (node (ref "U1") (pin "21") (pinfunction "PA22_21") (pintype "bidirectional"))
      (node (ref "U2") (pin "13") (pinfunction "SDO_13") (pintype "output"))
    )
    (net (code "29") (name "/SI_MOSI") (class "Default")
      (node (ref "JP8") (pin "5") (pinfunction "5_5") (pintype "passive"))
      (node (ref "U1") (pin "20") (pinfunction "PA19_20") (pintype "bidirectional"))
      (node (ref "U2") (pin "14") (pinfunction "SDI_14") (pintype "bidirectional"))
    )
    (net (code "30") (name "/SI_NIRQ") (class "Default")
      (node (ref "JP9") (pin "4") (pinfunction "4_4") (pintype "passive"))
      (node (ref "U1") (pin "23") (pinfunction "PA24_23") (pintype "bidirectional"))
      (node (ref "U2") (pin "11") (pinfunction "NIRQ_11") (pintype "output"))
    )
    (net (code "31") (name "/SI_NSEL") (class "Default")
      (node (ref "JP8") (pin "2") (pinfunction "2_2") (pintype "passive"))
      (node (ref "U1") (pin "19") (pinfunction "PA18_19") (pintype "bidirectional"))
      (node (ref "U2") (pin "15") (pinfunction "NSEL_15") (pintype "input"))
    )
    (net (code "32") (name "/SI_SCLK") (class "Default")
      (node (ref "JP8") (pin "3") (pinfunction "3_3") (pintype "passive"))
      (node (ref "U1") (pin "22") (pinfunction "PA23_22") (pintype "bidirectional"))
      (node (ref "U2") (pin "12") (pinfunction "SCLK_12") (pintype "input"))
    )
    (net (code "33") (name "/SI_SDN") (class "Default")
      (node (ref "JP9") (pin "5") (pinfunction "5_5") (pintype "passive"))
      (node (ref "U1") (pin "17") (pinfunction "PA16_17") (pintype "bidirectional"))
      (node (ref "U2") (pin "1") (pinfunction "SDN_1") (pintype "input"))
    )
    (net (code "34") (name "/STEPUP_IN") (class "Default")
      (node (ref "C14") (pin "1") (pinfunction "P$1_1") (pintype "passive"))
      (node (ref "C5") (pin "1") (pinfunction "P$1_1") (pintype "passive"))
      (node (ref "JP1") (pin "1") (pinfunction "1_1") (pintype "passive"))
      (node (ref "L1") (pin "2") (pinfunction "2_2") (pintype "passive"))
      (node (ref "R5") (pin "1") (pinfunction "1_1") (pintype "passive"))
      (node (ref "R6") (pin "1") (pinfunction "1_1") (pintype "passive"))
      (node (ref "U$2") (pin "A2") (pinfunction "-_A2") (pintype "bidirectional"))
      (node (ref "U3") (pin "4") (pinfunction "NSHDN_4") (pintype "bidirectional"))
      (node (ref "U3") (pin "8") (pinfunction "BATT_8") (pintype "bidirectional"))
    )
    (net (code "35") (name "/STEPUP_OUT") (class "Default")
      (node (ref "C4") (pin "1") (pinfunction "P$1_1") (pintype "passive"))
      (node (ref "JP2") (pin "2") (pinfunction "2_2") (pintype "passive"))
      (node (ref "R7") (pin "2") (pinfunction "2_2") (pintype "passive"))
      (node (ref "R8") (pin "2") (pinfunction "2_2") (pintype "passive"))
      (node (ref "U$5") (pin "A1") (pinfunction "+_A1") (pintype "bidirectional"))
      (node (ref "U3") (pin "7") (pinfunction "OUT_7") (pintype "bidirectional"))
    )
    (net (code "36") (name "/STM_SWDCLK") (class "Default")
      (node (ref "JTAG2") (pin "4") (pinfunction "4_4") (pintype "passive"))
      (node (ref "U6") (pin "37") (pinfunction "PA14/JTCK/SWCLK_37") (pintype "bidirectional"))
    )
    (net (code "37") (name "/STM_SWDIO") (class "Default")
      (node (ref "JTAG2") (pin "2") (pinfunction "2_2") (pintype "passive"))
      (node (ref "U6") (pin "34") (pinfunction "PA13/JTMS_34") (pintype "bidirectional"))
    )
    (net (code "38") (name "/SWDCLK") (class "Default")
      (node (ref "JTAG1") (pin "4") (pinfunction "4_4") (pintype "passive"))
      (node (ref "U1") (pin "31") (pinfunction "PA30/SWCLK_31") (pintype "bidirectional"))
    )
    (net (code "39") (name "/SWDIO") (class "Default")
      (node (ref "JTAG1") (pin "2") (pinfunction "2_2") (pintype "passive"))
      (node (ref "U1") (pin "32") (pinfunction "PA31/SWDIO_32") (pintype "bidirectional"))
    )
    (net (code "40") (name "/TIME_1KHZ") (class "Default")
      (node (ref "C13") (pin "1") (pinfunction "P$1_1") (pintype "passive"))
      (node (ref "JP11") (pin "2") (pinfunction "2_2") (pintype "passive"))
      (node (ref "R2") (pin "1") (pinfunction "1_1") (pintype "passive"))
      (node (ref "U1") (pin "27") (pinfunction "PA28_27") (pintype "bidirectional"))
    )
    (net (code "41") (name "/USB_DM") (class "Default")
      (node (ref "R19") (pin "1") (pinfunction "1_1") (pintype "passive"))
      (node (ref "U6") (pin "32") (pinfunction "PA11/USB_DM_32") (pintype "bidirectional"))
    )
    (net (code "42") (name "/USB_DP") (class "Default")
      (node (ref "R12") (pin "1") (pinfunction "1_1") (pintype "passive"))
      (node (ref "U6") (pin "33") (pinfunction "PA12/USB_DP_33") (pintype "bidirectional"))
    )
    (net (code "43") (name "/USB_ENUMERATE") (class "Default")
      (node (ref "R21") (pin "1") (pinfunction "1_1") (pintype "passive"))
      (node (ref "U6") (pin "29") (pinfunction "PA8_29") (pintype "bidirectional"))
    )
    (net (code "44") (name "/VBUS") (class "Default")
      (node (ref "R11") (pin "2") (pinfunction "2_2") (pintype "passive"))
      (node (ref "R20") (pin "1") (pinfunction "1_1") (pintype "passive"))
      (node (ref "U6") (pin "26") (pinfunction "PB13_26") (pintype "bidirectional"))
    )
    (net (code "45") (name "/VDD_GPS") (class "Default")
      (node (ref "JP7") (pin "1") (pinfunction "1_1") (pintype "passive"))
      (node (ref "R17") (pin "1") (pinfunction "1_1") (pintype "passive"))
      (node (ref "R18") (pin "1") (pinfunction "1_1") (pintype "passive"))
      (node (ref "U$62") (pin "A2") (pinfunction "-_A2") (pintype "bidirectional"))
      (node (ref "U4") (pin "25_VDD_RF") (pinfunction "VDD_RF_25_VDD_RF") (pintype "power_in"))
      (node (ref "U4") (pin "27_VCC") (pinfunction "VCC_27_VCC") (pintype "power_in"))
      (node (ref "U4") (pin "5_VIO") (pinfunction "VIO_5_VIO") (pintype "bidirectional"))
    )
    (net (code "46") (name "/VDD_MEM") (class "Default")
      (node (ref "C12") (pin "1") (pinfunction "P$1_1") (pintype "passive"))
      (node (ref "JP5") (pin "1") (pinfunction "1_1") (pintype "passive"))
      (node (ref "R13") (pin "1") (pinfunction "1_1") (pintype "passive"))
      (node (ref "R14") (pin "1") (pinfunction "1_1") (pintype "passive"))
      (node (ref "U$48") (pin "A2") (pinfunction "-_A2") (pintype "bidirectional"))
      (node (ref "U5") (pin "8") (pinfunction "VDD_8") (pintype "power_in"))
    )
    (net (code "47") (name "/VDD_PA") (class "Default")
      (node (ref "L2") (pin "2") (pinfunction "2_2") (pintype "passive"))
      (node (ref "R22") (pin "1") (pinfunction "1_1") (pintype "passive"))
      (node (ref "R23") (pin "1") (pinfunction "1_1") (pintype "passive"))
      (node (ref "U$99") (pin "A2") (pinfunction "-_A2") (pintype "bidirectional"))
    )
    (net (code "48") (name "/VDD_RADIO") (class "Default")
      (node (ref "FB1") (pin "2") (pinfunction "P$2_2") (pintype "passive"))
      (node (ref "JP6") (pin "1") (pinfunction "1_1") (pintype "passive"))
      (node (ref "R15") (pin "1") (pinfunction "1_1") (pintype "passive"))
      (node (ref "R16") (pin "1") (pinfunction "1_1") (pintype "passive"))
      (node (ref "U$60") (pin "A2") (pinfunction "-_A2") (pintype "bidirectional"))
    )
    (net (code "49") (name "/VDD_SAMD20") (class "Default")
      (node (ref "C3") (pin "1") (pinfunction "P$1_1") (pintype "passive"))
      (node (ref "JP3") (pin "1") (pinfunction "1_1") (pintype "passive"))
      (node (ref "R10") (pin "1") (pinfunction "1_1") (pintype "passive"))
      (node (ref "R9") (pin "1") (pinfunction "1_1") (pintype "passive"))
      (node (ref "U$30") (pin "A2") (pinfunction "-_A2") (pintype "bidirectional"))
      (node (ref "U1") (pin "30") (pinfunction "VDD_30") (pintype "power_in"))
      (node (ref "U1") (pin "9") (pinfunction "VDD_ANA_9") (pintype "power_in"))
    )
    (net (code "50") (name "/VDD_STEPUP") (class "Default")
      (node (ref "JP1") (pin "2") (pinfunction "2_2") (pintype "passive"))
      (node (ref "JP13") (pin "1") (pinfunction "1_1") (pintype "passive"))
      (node (ref "JP14") (pin "1") (pinfunction "1_1") (pintype "passive"))
      (node (ref "JP16") (pin "1") (pinfunction "1_1") (pintype "passive"))
      (node (ref "R5") (pin "2") (pinfunction "2_2") (pintype "passive"))
      (node (ref "R6") (pin "2") (pinfunction "2_2") (pintype "passive"))
      (node (ref "U$2") (pin "A1") (pinfunction "+_A1") (pintype "bidirectional"))
      (node (ref "U6") (pin "17") (pinfunction "PA7_17") (pintype "bidirectional"))
    )
    (net (code "51") (name "1.2V") (class "Default")
      (node (ref "U1") (pin "14") (pinfunction "PA11_14") (pintype "bidirectional"))
    )
    (net (code "52") (name "1.8V") (class "Default")
      (node (ref "D1") (pin "A") (pinfunction "A_A") (pintype "passive"))
      (node (ref "JP2") (pin "1") (pinfunction "1_1") (pintype "passive"))
      (node (ref "JP3") (pin "2") (pinfunction "2_2") (pintype "passive"))
      (node (ref "JP5") (pin "2") (pinfunction "2_2") (pintype "passive"))
      (node (ref "JP6") (pin "2") (pinfunction "2_2") (pintype "passive"))
      (node (ref "JP7") (pin "2") (pinfunction "2_2") (pintype "passive"))
      (node (ref "JTAG1") (pin "1") (pinfunction "1_1") (pintype "passive"))
      (node (ref "R10") (pin "2") (pinfunction "2_2") (pintype "passive"))
      (node (ref "R13") (pin "2") (pinfunction "2_2") (pintype "passive"))
      (node (ref "R14") (pin "2") (pinfunction "2_2") (pintype "passive"))
      (node (ref "R15") (pin "2") (pinfunction "2_2") (pintype "passive"))
      (node (ref "R16") (pin "2") (pinfunction "2_2") (pintype "passive"))
      (node (ref "R17") (pin "2") (pinfunction "2_2") (pintype "passive"))
      (node (ref "R18") (pin "2") (pinfunction "2_2") (pintype "passive"))
      (node (ref "R7") (pin "1") (pinfunction "1_1") (pintype "passive"))
      (node (ref "R8") (pin "1") (pinfunction "1_1") (pintype "passive"))
      (node (ref "R9") (pin "2") (pinfunction "2_2") (pintype "passive"))
      (node (ref "U$30") (pin "A1") (pinfunction "+_A1") (pintype "bidirectional"))
      (node (ref "U$48") (pin "A1") (pinfunction "+_A1") (pintype "bidirectional"))
      (node (ref "U$5") (pin "A2") (pinfunction "-_A2") (pintype "bidirectional"))
      (node (ref "U$60") (pin "A1") (pinfunction "+_A1") (pintype "bidirectional"))
      (node (ref "U$62") (pin "A1") (pinfunction "+_A1") (pintype "bidirectional"))
      (node (ref "U6") (pin "18") (pinfunction "PB0_18") (pintype "bidirectional"))
    )
    (net (code "53") (name "3.3V") (class "Default")
      (node (ref "BTN1") (pin "2") (pinfunction "2_2") (pintype "bidirectional"))
      (node (ref "C23") (pin "1") (pinfunction "1_1") (pintype "passive"))
      (node (ref "C24") (pin "1") (pinfunction "1_1") (pintype "passive"))
      (node (ref "C25") (pin "1") (pinfunction "1_1") (pintype "passive"))
      (node (ref "C26") (pin "1") (pinfunction "1_1") (pintype "passive"))
      (node (ref "IC3") (pin "5") (pinfunction "OUT_5") (pintype "bidirectional"))
      (node (ref "JP14") (pin "2") (pinfunction "2_2") (pintype "passive"))
      (node (ref "JTAG2") (pin "1") (pinfunction "1_1") (pintype "passive"))
      (node (ref "R26") (pin "1") (pinfunction "1_1") (pintype "passive"))
      (node (ref "U6") (pin "1") (pinfunction "VBAT_1") (pintype "bidirectional"))
      (node (ref "U6") (pin "24") (pinfunction "VDD_24") (pintype "bidirectional"))
      (node (ref "U6") (pin "36") (pinfunction "VDD_36") (pintype "bidirectional"))
      (node (ref "U6") (pin "40") (pinfunction "PB4/JNTRST_40") (pintype "bidirectional"))
      (node (ref "U6") (pin "48") (pinfunction "VDD_48") (pintype "bidirectional"))
      (node (ref "U6") (pin "9") (pinfunction "VDDA_9") (pintype "bidirectional"))
    )
    (net (code "54") (name "5.0V") (class "Default")
      (node (ref "C19") (pin "1") (pinfunction "1_1") (pintype "passive"))
      (node (ref "C22") (pin "1") (pinfunction "1_1") (pintype "passive"))
      (node (ref "C28") (pin "1") (pinfunction "1_1") (pintype "passive"))
      (node (ref "C31") (pin "1") (pinfunction "1_1") (pintype "passive"))
      (node (ref "CN1") (pin "VBUS") (pinfunction "VBUS_VBUS") (pintype "power_in"))
      (node (ref "IC1") (pin "3") (pinfunction "IN_3") (pintype "input"))
      (node (ref "IC3") (pin "1") (pinfunction "IN_1") (pintype "bidirectional"))
      (node (ref "IC3") (pin "3") (pinfunction "EN_3") (pintype "bidirectional"))
      (node (ref "R20") (pin "2") (pinfunction "2_2") (pintype "passive"))
      (node (ref "U7") (pin "2") (pinfunction "IN_2") (pintype "power_in"))
    )
    (net (code "55") (name "GND") (class "Default")
      (node (ref "C10") (pin "2") (pinfunction "P$2_2") (pintype "passive"))
      (node (ref "C11") (pin "2") (pinfunction "P$2_2") (pintype "passive"))
      (node (ref "C12") (pin "2") (pinfunction "P$2_2") (pintype "passive"))
      (node (ref "C13") (pin "2") (pinfunction "P$2_2") (pintype "passive"))
      (node (ref "C14") (pin "2") (pinfunction "P$2_2") (pintype "passive"))
      (node (ref "C15") (pin "2") (pinfunction "P$2_2") (pintype "passive"))
      (node (ref "C16") (pin "2") (pinfunction "P$2_2") (pintype "passive"))
      (node (ref "C17") (pin "2") (pinfunction "P$2_2") (pintype "passive"))
      (node (ref "C18") (pin "2") (pinfunction "P$2_2") (pintype "passive"))
      (node (ref "C19") (pin "2") (pinfunction "2_2") (pintype "passive"))
      (node (ref "C2") (pin "2") (pinfunction "P$2_2") (pintype "passive"))
      (node (ref "C20") (pin "1") (pinfunction "1_1") (pintype "passive"))
      (node (ref "C21") (pin "1") (pinfunction "1_1") (pintype "passive"))
      (node (ref "C22") (pin "2") (pinfunction "2_2") (pintype "passive"))
      (node (ref "C23") (pin "2") (pinfunction "2_2") (pintype "passive"))
      (node (ref "C24") (pin "2") (pinfunction "2_2") (pintype "passive"))
      (node (ref "C25") (pin "2") (pinfunction "2_2") (pintype "passive"))
      (node (ref "C26") (pin "2") (pinfunction "2_2") (pintype "passive"))
      (node (ref "C27") (pin "2") (pinfunction "2_2") (pintype "passive"))
      (node (ref "C28") (pin "2") (pinfunction "2_2") (pintype "passive"))
      (node (ref "C29") (pin "2") (pinfunction "2_2") (pintype "passive"))
      (node (ref "C3") (pin "2") (pinfunction "P$2_2") (pintype "passive"))
      (node (ref "C30") (pin "2") (pinfunction "2_2") (pintype "passive"))
      (node (ref "C31") (pin "2") (pinfunction "2_2") (pintype "passive"))
      (node (ref "C32") (pin "2") (pinfunction "2_2") (pintype "passive"))
      (node (ref "C4") (pin "2") (pinfunction "P$2_2") (pintype "passive"))
      (node (ref "C5") (pin "2") (pinfunction "P$2_2") (pintype "passive"))
      (node (ref "C6") (pin "2") (pinfunction "P$2_2") (pintype "passive"))
      (node (ref "C8") (pin "2") (pinfunction "P$2_2") (pintype "passive"))
      (node (ref "C9") (pin "2") (pinfunction "P$2_2") (pintype "passive"))
      (node (ref "CN1") (pin "GND") (pinfunction "GND_GND") (pintype "power_in"))
      (node (ref "CN1") (pin "ID") (pinfunction "ID_ID") (pintype "bidirectional"))
      (node (ref "D2") (pin "C") (pinfunction "C_C") (pintype "passive"))
      (node (ref "D3") (pin "C") (pinfunction "C_C") (pintype "passive"))
      (node (ref "D4") (pin "C") (pinfunction "C_C") (pintype "passive"))
      (node (ref "D5") (pin "C") (pinfunction "C_C") (pintype "passive"))
      (node (ref "IC1") (pin "1") (pinfunction "ADJ_1") (pintype "input"))
      (node (ref "IC3") (pin "2") (pinfunction "GND_2") (pintype "bidirectional"))
      (node (ref "JP10") (pin "1") (pinfunction "1_1") (pintype "passive"))
      (node (ref "JP11") (pin "1") (pinfunction "1_1") (pintype "passive"))
      (node (ref "JP12") (pin "1") (pinfunction "1_1") (pintype "passive"))
      (node (ref "JP4") (pin "1") (pinfunction "1_1") (pintype "passive"))
      (node (ref "JP8") (pin "1") (pinfunction "1_1") (pintype "passive"))
      (node (ref "JP9") (pin "1") (pinfunction "1_1") (pintype "passive"))
      (node (ref "JTAG1") (pin "3") (pinfunction "3_3") (pintype "passive"))
      (node (ref "JTAG1") (pin "5") (pinfunction "5_5") (pintype "passive"))
      (node (ref "JTAG2") (pin "3") (pinfunction "3_3") (pintype "passive"))
      (node (ref "JTAG2") (pin "5") (pinfunction "5_5") (pintype "passive"))
      (node (ref "R11") (pin "1") (pinfunction "1_1") (pintype "passive"))
      (node (ref "R29") (pin "1") (pinfunction "1_1") (pintype "passive"))
      (node (ref "U$2") (pin "B1") (pinfunction "GND_B1") (pintype "bidirectional"))
      (node (ref "U$30") (pin "B1") (pinfunction "GND_B1") (pintype "bidirectional"))
      (node (ref "U$48") (pin "B1") (pinfunction "GND_B1") (pintype "bidirectional"))
      (node (ref "U$5") (pin "B1") (pinfunction "GND_B1") (pintype "bidirectional"))
      (node (ref "U$60") (pin "B1") (pinfunction "GND_B1") (pintype "bidirectional"))
      (node (ref "U$62") (pin "B1") (pinfunction "GND_B1") (pintype "bidirectional"))
      (node (ref "U$99") (pin "B1") (pinfunction "GND_B1") (pintype "bidirectional"))
      (node (ref "U1") (pin "10") (pinfunction "GND1_10") (pintype "power_in"))
      (node (ref "U1") (pin "28") (pinfunction "GND2_28") (pintype "power_in"))
      (node (ref "U1") (pin "33") (pinfunction "GND_33") (pintype "power_in"))
      (node (ref "U2") (pin "18") (pinfunction "GND2_18") (pintype "power_in"))
      (node (ref "U2") (pin "5") (pinfunction "NC/GND_5") (pintype "bidirectional"))
      (node (ref "U2") (pin "PAD") (pinfunction "GND_PAD") (pintype "power_in"))
      (node (ref "U3") (pin "2") (pinfunction "GNDA_2") (pintype "bidirectional"))
      (node (ref "U3") (pin "3") (pinfunction "GNDB_3") (pintype "bidirectional"))
      (node (ref "U3") (pin "5") (pinfunction "PGND_5") (pintype "bidirectional"))
      (node (ref "U3") (pin "PAD") (pinfunction "GND_PAD_PAD") (pintype "bidirectional"))
      (node (ref "U4") (pin "14_GND") (pinfunction "GND3_14_GND") (pintype "power_in"))
      (node (ref "U4") (pin "17_GND") (pinfunction "GND4_17_GND") (pintype "power_in"))
      (node (ref "U4") (pin "21_GND") (pinfunction "GND5_21_GND") (pintype "bidirectional"))
      (node (ref "U4") (pin "24_GND") (pinfunction "GND6_24_GND") (pintype "bidirectional"))
      (node (ref "U4") (pin "26_GND") (pinfunction "GND7_26_GND") (pintype "power_in"))
      (node (ref "U4") (pin "28_GND") (pinfunction "GND8_28_GND") (pintype "power_in"))
      (node (ref "U4") (pin "2_GND") (pinfunction "GND1_2_GND") (pintype "power_in"))
      (node (ref "U4") (pin "32_VDD_USB") (pinfunction "VDD_USB_32_VDD_USB") (pintype "bidirectional"))
      (node (ref "U4") (pin "33_GND") (pinfunction "GND9_33_GND") (pintype "power_in"))
      (node (ref "U4") (pin "34_GND") (pinfunction "GND10_34_GND") (pintype "power_in"))
      (node (ref "U4") (pin "35_GND") (pinfunction "GND11_35_GND") (pintype "bidirectional"))
      (node (ref "U4") (pin "36_GND") (pinfunction "GND12_36_GND") (pintype "bidirectional"))
      (node (ref "U4") (pin "4_GND") (pinfunction "GND2_4_GND") (pintype "power_in"))
      (node (ref "U5") (pin "4") (pinfunction "VSS_4") (pintype "power_in"))
      (node (ref "U5") (pin "PAD") (pinfunction "GND_PAD_PAD") (pintype "power_in"))
      (node (ref "U6") (pin "23") (pinfunction "VSS_23") (pintype "bidirectional"))
      (node (ref "U6") (pin "35") (pinfunction "VSS_35") (pintype "bidirectional"))
      (node (ref "U6") (pin "47") (pinfunction "VSS_47") (pintype "bidirectional"))
      (node (ref "U6") (pin "8") (pinfunction "VSSA_8") (pintype "bidirectional"))
      (node (ref "U7") (pin "3") (pinfunction "GND_3") (pintype "passive"))
      (node (ref "U7") (pin "6") (pinfunction "DAP_6") (pintype "passive"))
    )
    (net (code "56") (name "Net-(C1-P$1)") (class "Default")
      (node (ref "C1") (pin "1") (pinfunction "P$1_1") (pintype "passive"))
      (node (ref "U4") (pin "3_ANT_OUT") (pinfunction "ANT_OUT_3_ANT_OUT") (pintype "output"))
    )
    (net (code "57") (name "Net-(C1-P$2)") (class "Default")
      (node (ref "C1") (pin "2") (pinfunction "P$2_2") (pintype "passive"))
      (node (ref "U4") (pin "1_ANT_IN") (pinfunction "ANT_IN_1_ANT_IN") (pintype "input"))
    )
    (net (code "58") (name "Net-(C2-P$1)") (class "Default")
      (node (ref "C2") (pin "1") (pinfunction "P$1_1") (pintype "passive"))
      (node (ref "U1") (pin "29") (pinfunction "VDD_CORE_29") (pintype "power_in"))
    )
    (net (code "59") (name "Net-(C7-P$1)") (class "Default")
      (node (ref "C7") (pin "1") (pinfunction "P$1_1") (pintype "passive"))
      (node (ref "L3") (pin "2") (pinfunction "2_2") (pintype "passive"))
    )
    (net (code "60") (name "Net-(C7-P$2)") (class "Default")
      (node (ref "C7") (pin "2") (pinfunction "P$2_2") (pintype "passive"))
      (node (ref "L2") (pin "1") (pinfunction "1_1") (pintype "passive"))
      (node (ref "U2") (pin "4") (pinfunction "TX_4") (pintype "output"))
    )
    (net (code "61") (name "Net-(C8-P$1)") (class "Default")
      (node (ref "C8") (pin "1") (pinfunction "P$1_1") (pintype "passive"))
      (node (ref "L3") (pin "1") (pinfunction "1_1") (pintype "passive"))
      (node (ref "L4") (pin "2") (pinfunction "2_2") (pintype "passive"))
    )
    (net (code "62") (name "Net-(C9-P$1)") (class "Default")
      (node (ref "C9") (pin "1") (pinfunction "P$1_1") (pintype "passive"))
      (node (ref "L4") (pin "1") (pinfunction "1_1") (pintype "passive"))
      (node (ref "L5") (pin "2") (pinfunction "2_2") (pintype "passive"))
    )
    (net (code "63") (name "Net-(C15-P$1)") (class "Default")
      (node (ref "C15") (pin "1") (pinfunction "P$1_1") (pintype "passive"))
      (node (ref "R4") (pin "1") (pinfunction "1_1") (pintype "passive"))
      (node (ref "U4") (pin "13_RX") (pinfunction "RX_13_RX") (pintype "bidirectional"))
    )
    (net (code "64") (name "Net-(CN1-PadD+)") (class "Default")
      (node (ref "CN1") (pin "D+") (pinfunction "D+_D+") (pintype "bidirectional"))
      (node (ref "R12") (pin "2") (pinfunction "2_2") (pintype "passive"))
      (node (ref "R21") (pin "2") (pinfunction "2_2") (pintype "passive"))
    )
    (net (code "65") (name "Net-(CN1-PadD-)") (class "Default")
      (node (ref "CN1") (pin "D-") (pinfunction "D-_D-") (pintype "bidirectional"))
      (node (ref "R19") (pin "2") (pinfunction "2_2") (pintype "passive"))
    )
    (net (code "66") (name "Net-(D1-PadC)") (class "Default")
      (node (ref "D1") (pin "C") (pinfunction "C_C") (pintype "passive"))
      (node (ref "R1") (pin "2") (pinfunction "2_2") (pintype "passive"))
    )
    (net (code "67") (name "Net-(D2-PadA)") (class "Default")
      (node (ref "D2") (pin "A") (pinfunction "A_A") (pintype "passive"))
      (node (ref "R25") (pin "2") (pinfunction "2_2") (pintype "passive"))
    )
    (net (code "68") (name "Net-(D3-PadA)") (class "Default")
      (node (ref "D3") (pin "A") (pinfunction "A_A") (pintype "passive"))
      (node (ref "R26") (pin "2") (pinfunction "2_2") (pintype "passive"))
    )
    (net (code "69") (name "Net-(D4-PadA)") (class "Default")
      (node (ref "D4") (pin "A") (pinfunction "A_A") (pintype "passive"))
      (node (ref "R27") (pin "2") (pinfunction "2_2") (pintype "passive"))
    )
    (net (code "70") (name "Net-(D5-PadA)") (class "Default")
      (node (ref "D5") (pin "A") (pinfunction "A_A") (pintype "passive"))
      (node (ref "R28") (pin "2") (pinfunction "2_2") (pintype "passive"))
    )
    (net (code "71") (name "Net-(U3-LX)") (class "Default")
      (node (ref "L1") (pin "1") (pinfunction "1_1") (pintype "passive"))
      (node (ref "U3") (pin "6") (pinfunction "LX_6") (pintype "bidirectional"))
    )
    (net (code "72") (name "Net-(U4-TIMEPULSE{slash}TDO)") (class "Default")
      (node (ref "R2") (pin "2") (pinfunction "2_2") (pintype "passive"))
      (node (ref "U4") (pin "23_TIMEPULSE/TDO") (pinfunction "TIMEPULSE/TDO_23_TIMEPULSE/TDO") (pintype "bidirectional"))
    )
    (net (code "73") (name "Net-(U4-TX)") (class "Default")
      (node (ref "R3") (pin "1") (pinfunction "1_1") (pintype "passive"))
      (node (ref "U4") (pin "11_TX") (pinfunction "TX_11_TX") (pintype "bidirectional"))
    )
    (net (code "74") (name "Net-(U6-BOOT0)") (class "Default")
      (node (ref "BTN1") (pin "1") (pinfunction "1_1") (pintype "bidirectional"))
      (node (ref "R29") (pin "2") (pinfunction "2_2") (pintype "passive"))
      (node (ref "U6") (pin "44") (pinfunction "BOOT0_44") (pintype "bidirectional"))
    )
    (net (code "75") (name "Net-(U6-PD0{slash}OSC_IN)") (class "Default")
      (node (ref "C20") (pin "2") (pinfunction "2_2") (pintype "passive"))
      (node (ref "U6") (pin "5") (pinfunction "PD0/OSC_IN_5") (pintype "bidirectional"))
      (node (ref "Y1") (pin "3") (pinfunction "2_3") (pintype "passive"))
    )
    (net (code "76") (name "Net-(U6-PD1{slash}OSC_OUT)") (class "Default")
      (node (ref "C21") (pin "2") (pinfunction "2_2") (pintype "passive"))
      (node (ref "U6") (pin "6") (pinfunction "PD1/OSC_OUT_6") (pintype "bidirectional"))
      (node (ref "Y1") (pin "1") (pinfunction "1_1") (pintype "passive"))
    )
    (net (code "77") (name "unconnected-(JTAG1-Pad6)") (class "Default")
      (node (ref "JTAG1") (pin "6") (pinfunction "6_6") (pintype "passive"))
    )
    (net (code "78") (name "unconnected-(JTAG1-Pad7)") (class "Default")
      (node (ref "JTAG1") (pin "7") (pinfunction "7_7") (pintype "passive"))
    )
    (net (code "79") (name "unconnected-(JTAG1-Pad8)") (class "Default")
      (node (ref "JTAG1") (pin "8") (pinfunction "8_8") (pintype "passive"))
    )
    (net (code "80") (name "unconnected-(JTAG1-Pad9)") (class "Default")
      (node (ref "JTAG1") (pin "9") (pinfunction "9_9") (pintype "passive"))
    )
    (net (code "81") (name "unconnected-(JTAG2-Pad6)") (class "Default")
      (node (ref "JTAG2") (pin "6") (pinfunction "6_6") (pintype "passive"))
    )
    (net (code "82") (name "unconnected-(JTAG2-Pad7)") (class "Default")
      (node (ref "JTAG2") (pin "7") (pinfunction "7_7") (pintype "passive"))
    )
    (net (code "83") (name "unconnected-(JTAG2-Pad8)") (class "Default")
      (node (ref "JTAG2") (pin "8") (pinfunction "8_8") (pintype "passive"))
    )
    (net (code "84") (name "unconnected-(JTAG2-Pad9)") (class "Default")
      (node (ref "JTAG2") (pin "9") (pinfunction "9_9") (pintype "passive"))
    )
    (net (code "85") (name "unconnected-(JTAG2-Pad10)") (class "Default")
      (node (ref "JTAG2") (pin "10") (pinfunction "10_10") (pintype "passive"))
    )
    (net (code "86") (name "unconnected-(U1-PA02-Pad3)") (class "Default")
      (node (ref "U1") (pin "3") (pinfunction "PA02_3") (pintype "bidirectional"))
    )
    (net (code "87") (name "unconnected-(U1-PA03-Pad4)") (class "Default")
      (node (ref "U1") (pin "4") (pinfunction "PA03_4") (pintype "bidirectional"))
    )
    (net (code "88") (name "unconnected-(U1-PA05-Pad6)") (class "Default")
      (node (ref "U1") (pin "6") (pinfunction "PA05_6") (pintype "bidirectional"))
    )
    (net (code "89") (name "unconnected-(U1-PA14-Pad15)") (class "Default")
      (node (ref "U1") (pin "15") (pinfunction "PA14_15") (pintype "bidirectional"))
    )
    (net (code "90") (name "unconnected-(U1-PA15-Pad16)") (class "Default")
      (node (ref "U1") (pin "16") (pinfunction "PA15_16") (pintype "bidirectional"))
    )
    (net (code "91") (name "unconnected-(U2-GPIO2-Pad19)") (class "Default")
      (node (ref "U2") (pin "19") (pinfunction "GPIO2_19") (pintype "bidirectional"))
    )
    (net (code "92") (name "unconnected-(U2-GPIO3-Pad20)") (class "Default")
      (node (ref "U2") (pin "20") (pinfunction "GPIO3_20") (pintype "bidirectional"))
    )
    (net (code "93") (name "unconnected-(U2-NC-Pad2)") (class "Default")
      (node (ref "U2") (pin "2") (pinfunction "NC_2") (pintype "no_connect"))
    )
    (net (code "94") (name "unconnected-(U2-NC -Pad3)") (class "Default")
      (node (ref "U2") (pin "3") (pinfunction "NC _3") (pintype "no_connect"))
    )
    (net (code "95") (name "unconnected-(U2-TXRAMP-Pad7)") (class "Default")
      (node (ref "U2") (pin "7") (pinfunction "TXRAMP_7") (pintype "bidirectional"))
    )
    (net (code "96") (name "unconnected-(U2-XOUT-Pad16)") (class "Default")
      (node (ref "U2") (pin "16") (pinfunction "XOUT_16") (pintype "output"))
    )
    (net (code "97") (name "unconnected-(U4-CFG-Pad31_CFG)") (class "Default")
      (node (ref "U4") (pin "31_CFG") (pinfunction "CFG_31_CFG") (pintype "bidirectional"))
    )
    (net (code "98") (name "unconnected-(U4-CFG_GPS0{slash}SCK-Pad9_CFG_GPS0_SCK)") (class "Default")
      (node (ref "U4") (pin "9_CFG_GPS0_SCK") (pinfunction "CFG_GPS0/SCK_9_CFG_GPS0_SCK") (pintype "bidirectional"))
    )
    (net (code "99") (name "unconnected-(U4-EXT_INTERRUPT-Pad29_EXT_INTERRUPT)") (class "Default")
      (node (ref "U4") (pin "29_EXT_INTERRUPT") (pinfunction "EXT_INTERRUPT_29_EXT_INTERRUPT") (pintype "bidirectional"))
    )
    (net (code "100") (name "unconnected-(U4-SAFEBOOT_N{slash}TDI-Pad20_SAFEBOOT_N{slash}TDI)") (class "Default")
      (node (ref "U4") (pin "20_SAFEBOOT_N/TDI") (pinfunction "SAFEBOOT_N/TDI_20_SAFEBOOT_N/TDI") (pintype "bidirectional"))
    )
    (net (code "101") (name "unconnected-(U4-SCL-Pad19_SCL)") (class "Default")
      (node (ref "U4") (pin "19_SCL") (pinfunction "SCL_19_SCL") (pintype "bidirectional"))
    )
    (net (code "102") (name "unconnected-(U4-SDA-Pad18_SDA)") (class "Default")
      (node (ref "U4") (pin "18_SDA") (pinfunction "SDA_18_SDA") (pintype "bidirectional"))
    )
    (net (code "103") (name "unconnected-(U4-SI-Pad16_SI)") (class "Default")
      (node (ref "U4") (pin "16_SI") (pinfunction "SI_16_SI") (pintype "bidirectional"))
    )
    (net (code "104") (name "unconnected-(U4-SO-Pad8_SO)") (class "Default")
      (node (ref "U4") (pin "8_SO") (pinfunction "SO_8_SO") (pintype "bidirectional"))
    )
    (net (code "105") (name "unconnected-(U4-SPI_CS-Pad10_SPI_SELECT)") (class "Default")
      (node (ref "U4") (pin "10_SPI_SELECT") (pinfunction "SPI_CS_10_SPI_SELECT") (pintype "bidirectional"))
    )
    (net (code "106") (name "unconnected-(U4-TCK-Pad22_TCK)") (class "Default")
      (node (ref "U4") (pin "22_TCK") (pinfunction "TCK_22_TCK") (pintype "bidirectional"))
    )
    (net (code "107") (name "unconnected-(U4-USB_DM-Pad7_USB_DM)") (class "Default")
      (node (ref "U4") (pin "7_USB_DM") (pinfunction "USB_DM_7_USB_DM") (pintype "bidirectional"))
    )
    (net (code "108") (name "unconnected-(U4-USB_DP-Pad6_USB_DP)") (class "Default")
      (node (ref "U4") (pin "6_USB_DP") (pinfunction "USB_DP_6_USB_DP") (pintype "bidirectional"))
    )
    (net (code "109") (name "unconnected-(U4-V_BCKP-Pad15_V_BCKUP)") (class "Default")
      (node (ref "U4") (pin "15_V_BCKUP") (pinfunction "V_BCKP_15_V_BCKUP") (pintype "bidirectional"))
    )
    (net (code "110") (name "unconnected-(U4-V_EN-Pad30_V_EN)") (class "Default")
      (node (ref "U4") (pin "30_V_EN") (pinfunction "V_EN_30_V_EN") (pintype "bidirectional"))
    )
    (net (code "111") (name "unconnected-(U4-V_TH-Pad12_V_TH)") (class "Default")
      (node (ref "U4") (pin "12_V_TH") (pinfunction "V_TH_12_V_TH") (pintype "bidirectional"))
    )
    (net (code "112") (name "unconnected-(U5-IO3{slash}RESETN-Pad7)") (class "Default")
      (node (ref "U5") (pin "7") (pinfunction "IO3/RESETN_7") (pintype "output"))
    )
    (net (code "113") (name "unconnected-(U6-NRST-Pad7)") (class "Default")
      (node (ref "U6") (pin "7") (pinfunction "NRST_7") (pintype "bidirectional"))
    )
    (net (code "114") (name "unconnected-(U6-PA9-Pad30)") (class "Default")
      (node (ref "U6") (pin "30") (pinfunction "PA9_30") (pintype "bidirectional"))
    )
    (net (code "115") (name "unconnected-(U6-PA10-Pad31)") (class "Default")
      (node (ref "U6") (pin "31") (pinfunction "PA10_31") (pintype "bidirectional"))
    )
    (net (code "116") (name "unconnected-(U6-PA15{slash}JTDI-Pad38)") (class "Default")
      (node (ref "U6") (pin "38") (pinfunction "PA15/JTDI_38") (pintype "bidirectional"))
    )
    (net (code "117") (name "unconnected-(U6-PB3{slash}JTDO-Pad39)") (class "Default")
      (node (ref "U6") (pin "39") (pinfunction "PB3/JTDO_39") (pintype "bidirectional"))
    )
    (net (code "118") (name "unconnected-(U6-PB5-Pad41)") (class "Default")
      (node (ref "U6") (pin "41") (pinfunction "PB5_41") (pintype "bidirectional"))
    )
    (net (code "119") (name "unconnected-(U6-PB6-Pad42)") (class "Default")
      (node (ref "U6") (pin "42") (pinfunction "PB6_42") (pintype "bidirectional"))
    )
    (net (code "120") (name "unconnected-(U6-PB7-Pad43)") (class "Default")
      (node (ref "U6") (pin "43") (pinfunction "PB7_43") (pintype "bidirectional"))
    )
    (net (code "121") (name "unconnected-(U6-PB8-Pad45)") (class "Default")
      (node (ref "U6") (pin "45") (pinfunction "PB8_45") (pintype "bidirectional"))
    )
    (net (code "122") (name "unconnected-(U6-PB9-Pad46)") (class "Default")
      (node (ref "U6") (pin "46") (pinfunction "PB9_46") (pintype "bidirectional"))
    )
    (net (code "123") (name "unconnected-(U6-PB12-Pad25)") (class "Default")
      (node (ref "U6") (pin "25") (pinfunction "PB12_25") (pintype "bidirectional"))
    )
    (net (code "124") (name "unconnected-(U6-PB14-Pad27)") (class "Default")
      (node (ref "U6") (pin "27") (pinfunction "PB14_27") (pintype "bidirectional"))
    )
    (net (code "125") (name "unconnected-(U6-PB15-Pad28)") (class "Default")
      (node (ref "U6") (pin "28") (pinfunction "PB15_28") (pintype "bidirectional"))
    )
    (net (code "126") (name "unconnected-(U6-PC13{slash}TAMPER_RTC-Pad2)") (class "Default")
      (node (ref "U6") (pin "2") (pinfunction "PC13/TAMPER_RTC_2") (pintype "bidirectional"))
    )
    (net (code "127") (name "unconnected-(U6-PC14{slash}OSC32_IN-Pad3)") (class "Default")
      (node (ref "U6") (pin "3") (pinfunction "PC14/OSC32_IN_3") (pintype "bidirectional"))
    )
    (net (code "128") (name "unconnected-(U6-PC15{slash}OSC32_OUT-Pad4)") (class "Default")
      (node (ref "U6") (pin "4") (pinfunction "PC15/OSC32_OUT_4") (pintype "bidirectional"))
    )
  )
)
